# Hekr_V1_1.net
KiCad netlist of a schematic drawn in Altium Designer
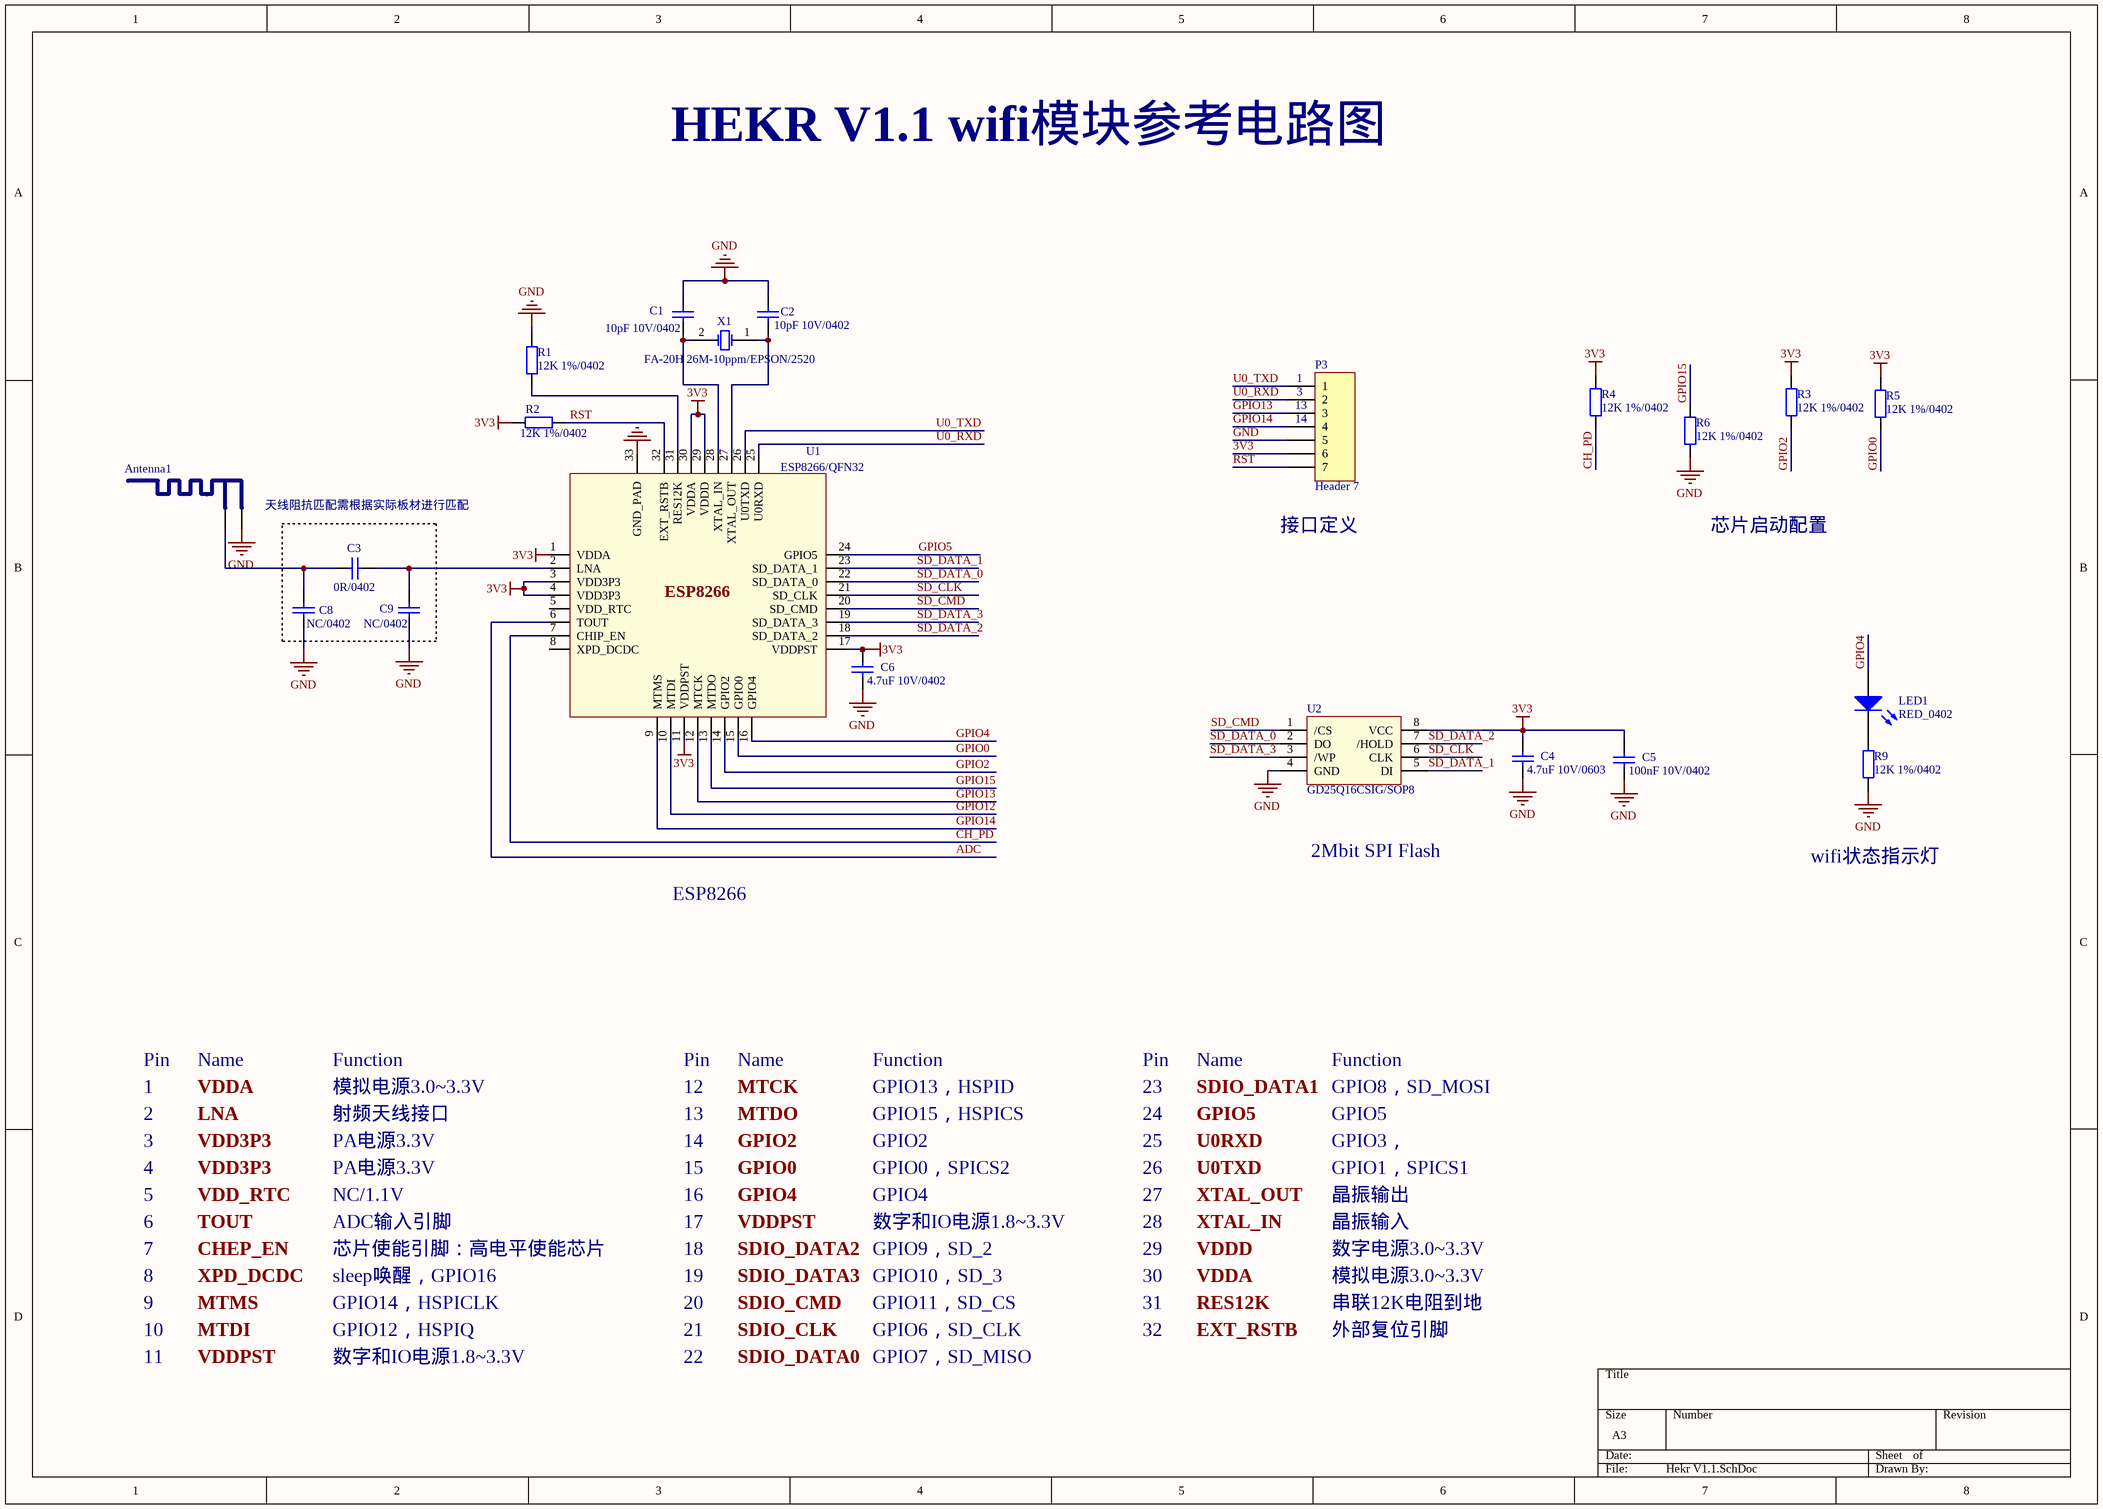
[diagram p0: Hekr V1.1.SchDoc]

(export (version "E")
  (design (tool "Eeschema 10.0.6"))
  (components
    (comp (ref "Antenna1")
      (value "F Antenna")
      (footprint "2.4G_ANTENNA_2")
      (libsource (lib "LT8900") (part "F Antenna"))
    )
    (comp (ref "C1")
      (value "10pF 10V/0402")
      (footprint "C_0402")
      (description "C0603")
      (fields (field (name "PUBLISHER") "Altium Limited"))
      (libsource (lib "PersonalLib_Chen_Miscellaneous") (part "C0603"))
    )
    (comp (ref "C2")
      (value "10pF 10V/0402")
      (footprint "C_0402")
      (description "C0603")
      (fields (field (name "PUBLISHER") "Altium Limited"))
      (libsource (lib "PersonalLib_Chen_Miscellaneous") (part "C0603"))
    )
    (comp (ref "C3")
      (value "0R/0402")
      (footprint "C_0402")
      (description "C0603")
      (fields (field (name "PUBLISHER") "Altium Limited"))
      (libsource (lib "PersonalLib_Chen_Miscellaneous") (part "C0603"))
    )
    (comp (ref "C4")
      (value "4.7uF 10V/0603")
      (footprint "C_0805")
      (description "C0603")
      (fields (field (name "PUBLISHER") "Altium Limited"))
      (libsource (lib "PersonalLib_Chen_Miscellaneous") (part "C0603"))
    )
    (comp (ref "C5")
      (value "100nF 10V/0402")
      (footprint "C_0402")
      (description "C0603")
      (fields (field (name "PUBLISHER") "Altium Limited"))
      (libsource (lib "PersonalLib_Chen_Miscellaneous") (part "C0603"))
    )
    (comp (ref "C6")
      (value "4.7uF 10V/0402")
      (footprint "C_0402")
      (description "C0603")
      (fields (field (name "PUBLISHER") "Altium Limited"))
      (libsource (lib "PersonalLib_Chen_Miscellaneous") (part "C0603"))
    )
    (comp (ref "C8")
      (value "NC/0402")
      (footprint "C_0402")
      (description "C0603")
      (fields (field (name "PUBLISHER") "Altium Limited"))
      (libsource (lib "PersonalLib_Chen_Miscellaneous") (part "C0603"))
    )
    (comp (ref "C9")
      (value "NC/0402")
      (footprint "C_0402")
      (description "C0603")
      (fields (field (name "PUBLISHER") "Altium Limited"))
      (libsource (lib "PersonalLib_Chen_Miscellaneous") (part "C0603"))
    )
    (comp (ref "LED1")
      (value "RED_0402")
      (footprint "LED_0402")
      (description "Typical RED, GREEN, YELLOW, AMBER GaAs LED")
      (fields (field (name "PUBLISHER") "Altium Limited"))
      (libsource (lib "Miscellaneous Devices") (part "LED2"))
    )
    (comp (ref "P3")
      (value "Header 7")
      (footprint "DIP6-2.0")
      (description "Header, 7-Pin")
      (fields (field (name "PUBLISHER") "Altium Limited"))
      (libsource (lib "Miscellaneous Connectors") (part "Header 7"))
    )
    (comp (ref "R1")
      (value "12K 1%/0402")
      (footprint "R_0402")
      (description "Resistor")
      (fields (field (name "Comment") "12K/0402") (field (name "PUBLISHER") "Altium Limited"))
      (libsource (lib "") (part "Res2_1"))
    )
    (comp (ref "R2")
      (value "12K 1%/0402")
      (footprint "R_0402")
      (description "Resistor")
      (fields (field (name "Comment") "4.7K/0402") (field (name "PUBLISHER") "Altium Limited"))
      (libsource (lib "Miscellaneous Devices") (part "Res2"))
    )
    (comp (ref "R3")
      (value "12K 1%/0402")
      (footprint "R_0402")
      (description "Resistor")
      (fields (field (name "Comment") "4.7K/0402") (field (name "PUBLISHER") "Altium Limited"))
      (libsource (lib "") (part "Res2_1"))
    )
    (comp (ref "R4")
      (value "12K 1%/0402")
      (footprint "R_0402")
      (description "Resistor")
      (fields (field (name "Comment") "4.7K/0402") (field (name "PUBLISHER") "Altium Limited"))
      (libsource (lib "") (part "Res2_1"))
    )
    (comp (ref "R5")
      (value "12K 1%/0402")
      (footprint "R_0402")
      (description "Resistor")
      (fields (field (name "Comment") "4.7K/0402") (field (name "PUBLISHER") "Altium Limited"))
      (libsource (lib "") (part "Res2_1"))
    )
    (comp (ref "R6")
      (value "12K 1%/0402")
      (footprint "R_0402")
      (description "Resistor")
      (fields (field (name "Comment") "4.7K/0402") (field (name "PUBLISHER") "Altium Limited"))
      (libsource (lib "") (part "Res2_1"))
    )
    (comp (ref "R9")
      (value "12K 1%/0402")
      (footprint "R_0402")
      (description "Resistor")
      (fields (field (name "Comment") "1K/0402") (field (name "PUBLISHER") "Altium Limited"))
      (libsource (lib "") (part "Res2_1"))
    )
    (comp (ref "U1")
      (value "ESP8266/QFN32")
      (footprint "ESP8266")
      (libsource (lib "ESP8266 IPEX") (part "ESP8266/QFN32"))
    )
    (comp (ref "U2")
      (value "GD25Q16CSIG/SOP8")
      (footprint "GD25Q16/64")
      (libsource (lib "RT5350模块") (part "GD25Q64BSIG"))
    )
    (comp (ref "X1")
      (value "FA-20H 26M-10ppm/EPSON/2520")
      (footprint "XTAL_2520")
      (description "Crystal Oscillator")
      (fields (field (name "PUBLISHER") "Altium Limited"))
      (libsource (lib "Miscellaneous Devices") (part "XTAL"))
    )
  )
  (nets
    (net (code "1") (name "/ADC") (class "Default")
      (node (ref "U1") (pin "6") (pinfunction "TOUT_6") (pintype "passive"))
    )
    (net (code "2") (name "/CH_PD") (class "Default")
      (node (ref "R4") (pin "1") (pinfunction "1_1") (pintype "passive"))
      (node (ref "U1") (pin "7") (pinfunction "CHIP_EN_7") (pintype "passive"))
    )
    (net (code "3") (name "/GPIO0") (class "Default")
      (node (ref "R5") (pin "1") (pinfunction "1_1") (pintype "passive"))
      (node (ref "U1") (pin "15") (pinfunction "GPIO0_15") (pintype "passive"))
    )
    (net (code "4") (name "/GPIO2") (class "Default")
      (node (ref "R3") (pin "1") (pinfunction "1_1") (pintype "passive"))
      (node (ref "U1") (pin "14") (pinfunction "GPIO2_14") (pintype "passive"))
    )
    (net (code "5") (name "/GPIO4") (class "Default")
      (node (ref "LED1") (pin "1") (pinfunction "A_1") (pintype "passive"))
      (node (ref "U1") (pin "16") (pinfunction "GPIO4_16") (pintype "passive"))
    )
    (net (code "6") (name "/GPIO5") (class "Default")
      (node (ref "U1") (pin "24") (pinfunction "GPIO5_24") (pintype "passive"))
    )
    (net (code "7") (name "/GPIO12") (class "Default")
      (node (ref "U1") (pin "10") (pinfunction "MTDI_10") (pintype "passive"))
    )
    (net (code "8") (name "/GPIO13") (class "Default")
      (node (ref "P3") (pin "3") (pinfunction "3_3") (pintype "passive"))
      (node (ref "U1") (pin "12") (pinfunction "MTCK_12") (pintype "passive"))
    )
    (net (code "9") (name "/GPIO14") (class "Default")
      (node (ref "P3") (pin "4") (pinfunction "4_4") (pintype "passive"))
      (node (ref "U1") (pin "9") (pinfunction "MTMS_9") (pintype "passive"))
    )
    (net (code "10") (name "/GPIO15") (class "Default")
      (node (ref "R6") (pin "2") (pinfunction "2_2") (pintype "passive"))
      (node (ref "U1") (pin "13") (pinfunction "MTDO_13") (pintype "passive"))
    )
    (net (code "11") (name "/RST") (class "Default")
      (node (ref "P3") (pin "7") (pinfunction "7_7") (pintype "passive"))
      (node (ref "R2") (pin "1") (pinfunction "1_1") (pintype "passive"))
      (node (ref "U1") (pin "32") (pinfunction "EXT_RSTB_32") (pintype "passive"))
    )
    (net (code "12") (name "/SD_CLK") (class "Default")
      (node (ref "U1") (pin "21") (pinfunction "SD_CLK_21") (pintype "passive"))
      (node (ref "U2") (pin "6") (pinfunction "CLK_6") (pintype "passive"))
    )
    (net (code "13") (name "/SD_CMD") (class "Default")
      (node (ref "U1") (pin "20") (pinfunction "SD_CMD_20") (pintype "passive"))
      (node (ref "U2") (pin "1") (pinfunction "/CS_1") (pintype "passive"))
    )
    (net (code "14") (name "/SD_DATA_0") (class "Default")
      (node (ref "U1") (pin "22") (pinfunction "SD_DATA_0_22") (pintype "passive"))
      (node (ref "U2") (pin "2") (pinfunction "DO_2") (pintype "passive"))
    )
    (net (code "15") (name "/SD_DATA_1") (class "Default")
      (node (ref "U1") (pin "23") (pinfunction "SD_DATA_1_23") (pintype "passive"))
      (node (ref "U2") (pin "5") (pinfunction "DI_5") (pintype "passive"))
    )
    (net (code "16") (name "/SD_DATA_2") (class "Default")
      (node (ref "U1") (pin "18") (pinfunction "SD_DATA_2_18") (pintype "passive"))
      (node (ref "U2") (pin "7") (pinfunction "/HOLD_7") (pintype "passive"))
    )
    (net (code "17") (name "/SD_DATA_3") (class "Default")
      (node (ref "U1") (pin "19") (pinfunction "SD_DATA_3_19") (pintype "passive"))
      (node (ref "U2") (pin "3") (pinfunction "/WP_3") (pintype "passive"))
    )
    (net (code "18") (name "/U0_RXD") (class "Default")
      (node (ref "P3") (pin "2") (pinfunction "2_2") (pintype "passive"))
      (node (ref "U1") (pin "25") (pinfunction "U0RXD_25") (pintype "passive"))
    )
    (net (code "19") (name "/U0_TXD") (class "Default")
      (node (ref "P3") (pin "1") (pinfunction "1_1") (pintype "passive"))
      (node (ref "U1") (pin "26") (pinfunction "U0TXD_26") (pintype "passive"))
    )
    (net (code "20") (name "3V3") (class "Default")
      (node (ref "C4") (pin "2") (pinfunction "2_2") (pintype "passive"))
      (node (ref "C5") (pin "2") (pinfunction "2_2") (pintype "passive"))
      (node (ref "C6") (pin "2") (pinfunction "2_2") (pintype "passive"))
      (node (ref "P3") (pin "6") (pinfunction "6_6") (pintype "passive"))
      (node (ref "R2") (pin "2") (pinfunction "2_2") (pintype "passive"))
      (node (ref "R3") (pin "2") (pinfunction "2_2") (pintype "passive"))
      (node (ref "R4") (pin "2") (pinfunction "2_2") (pintype "passive"))
      (node (ref "R5") (pin "2") (pinfunction "2_2") (pintype "passive"))
      (node (ref "U1") (pin "1") (pinfunction "VDDA_1") (pintype "passive"))
      (node (ref "U1") (pin "11") (pinfunction "VDDPST_11") (pintype "passive"))
      (node (ref "U1") (pin "17") (pinfunction "VDDPST_17") (pintype "passive"))
      (node (ref "U1") (pin "29") (pinfunction "VDDD_29") (pintype "passive"))
      (node (ref "U1") (pin "3") (pinfunction "VDD3P3_3") (pintype "passive"))
      (node (ref "U1") (pin "30") (pinfunction "VDDA_30") (pintype "passive"))
      (node (ref "U1") (pin "4") (pinfunction "VDD3P3_4") (pintype "passive"))
      (node (ref "U2") (pin "8") (pinfunction "VCC_8") (pintype "passive"))
    )
    (net (code "21") (name "GND") (class "Default")
      (node (ref "Antenna1") (pin "2") (pinfunction "2_2") (pintype "passive"))
      (node (ref "C1") (pin "2") (pinfunction "2_2") (pintype "passive"))
      (node (ref "C2") (pin "2") (pinfunction "2_2") (pintype "passive"))
      (node (ref "C4") (pin "1") (pinfunction "1_1") (pintype "passive"))
      (node (ref "C5") (pin "1") (pinfunction "1_1") (pintype "passive"))
      (node (ref "C6") (pin "1") (pinfunction "1_1") (pintype "passive"))
      (node (ref "C8") (pin "1") (pinfunction "1_1") (pintype "passive"))
      (node (ref "C9") (pin "1") (pinfunction "1_1") (pintype "passive"))
      (node (ref "P3") (pin "5") (pinfunction "5_5") (pintype "passive"))
      (node (ref "R1") (pin "2") (pinfunction "2_2") (pintype "passive"))
      (node (ref "R6") (pin "1") (pinfunction "1_1") (pintype "passive"))
      (node (ref "R9") (pin "1") (pinfunction "1_1") (pintype "passive"))
      (node (ref "U1") (pin "33") (pinfunction "GND_PAD_33") (pintype "passive"))
      (node (ref "U2") (pin "4") (pinfunction "GND_4") (pintype "passive"))
    )
    (net (code "22") (name "Net-(Antenna1-Pad1)") (class "Default")
      (node (ref "Antenna1") (pin "1") (pinfunction "1_1") (pintype "passive"))
      (node (ref "C3") (pin "1") (pinfunction "1_1") (pintype "passive"))
      (node (ref "C8") (pin "2") (pinfunction "2_2") (pintype "passive"))
    )
    (net (code "23") (name "Net-(LED1-K)") (class "Default")
      (node (ref "LED1") (pin "2") (pinfunction "K_2") (pintype "passive"))
      (node (ref "R9") (pin "2") (pinfunction "2_2") (pintype "passive"))
    )
    (net (code "24") (name "Net-(U1-LNA)") (class "Default")
      (node (ref "C3") (pin "2") (pinfunction "2_2") (pintype "passive"))
      (node (ref "C9") (pin "2") (pinfunction "2_2") (pintype "passive"))
      (node (ref "U1") (pin "2") (pinfunction "LNA_2") (pintype "passive"))
    )
    (net (code "25") (name "Net-(U1-RES12K)") (class "Default")
      (node (ref "R1") (pin "1") (pinfunction "1_1") (pintype "passive"))
      (node (ref "U1") (pin "31") (pinfunction "RES12K_31") (pintype "passive"))
    )
    (net (code "26") (name "Net-(U1-XTAL_IN)") (class "Default")
      (node (ref "C1") (pin "1") (pinfunction "1_1") (pintype "passive"))
      (node (ref "U1") (pin "28") (pinfunction "XTAL_IN_28") (pintype "passive"))
      (node (ref "X1") (pin "2") (pinfunction "OSC2_2") (pintype "passive"))
    )
    (net (code "27") (name "Net-(U1-XTAL_OUT)") (class "Default")
      (node (ref "C2") (pin "1") (pinfunction "1_1") (pintype "passive"))
      (node (ref "U1") (pin "27") (pinfunction "XTAL_OUT_27") (pintype "passive"))
      (node (ref "X1") (pin "1") (pinfunction "OSC1_1") (pintype "passive"))
    )
    (net (code "28") (name "unconnected-(U1-VDD_RTC-Pad5)") (class "Default")
      (node (ref "U1") (pin "5") (pinfunction "VDD_RTC_5") (pintype "passive"))
    )
    (net (code "29") (name "unconnected-(U1-XPD_DCDC-Pad8)") (class "Default")
      (node (ref "U1") (pin "8") (pinfunction "XPD_DCDC_8") (pintype "passive"))
    )
  )
)
